# lvds_drv_e.net
KiCad netlist of a schematic drawn in Altium Designer
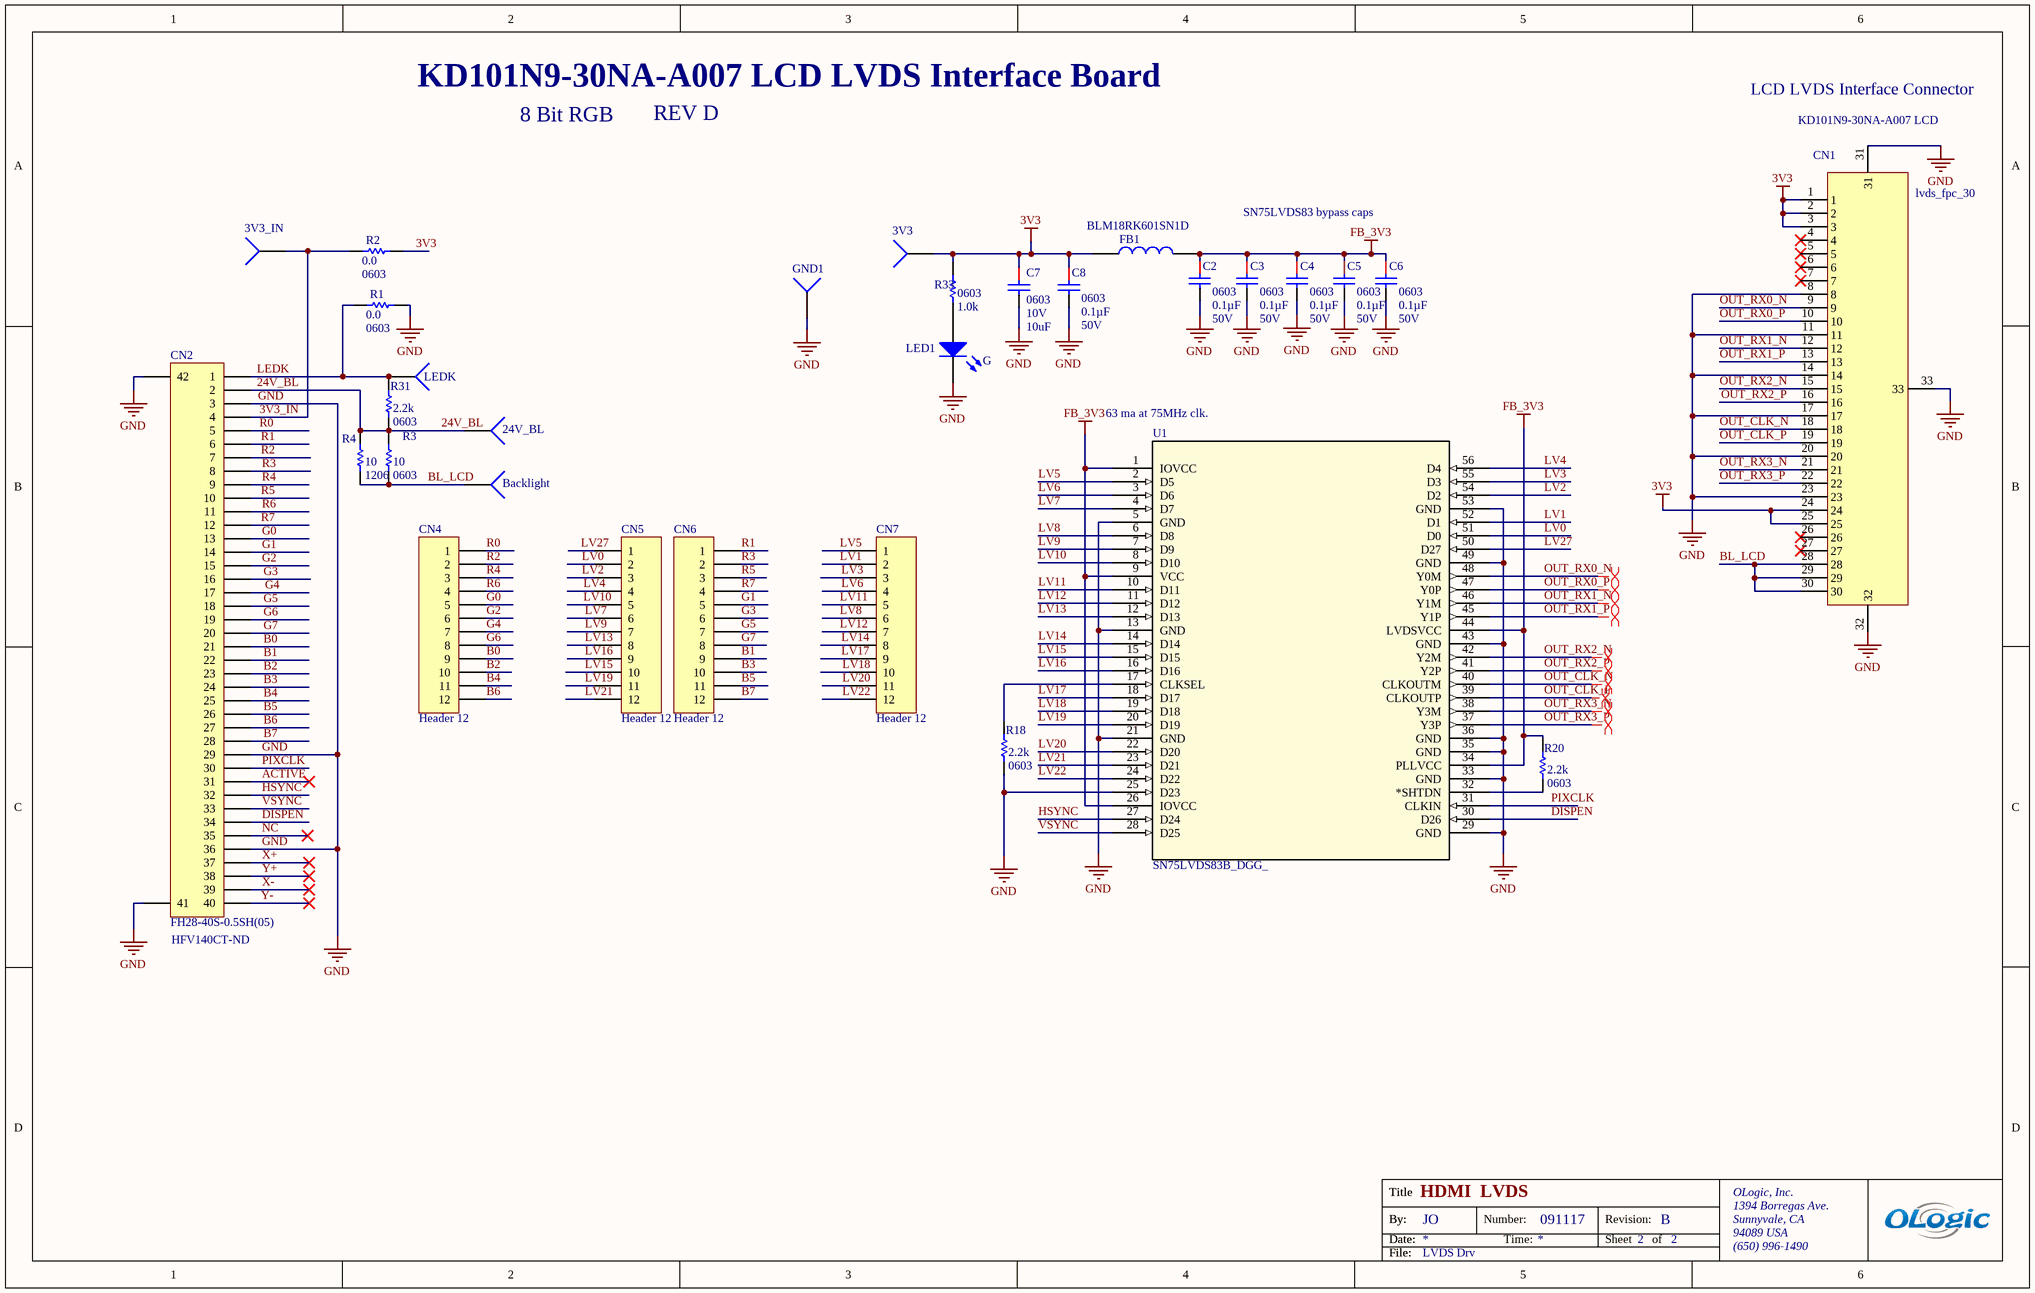
[diagram p0: lvds_drv_e.SchDoc]

(export (version "E")
  (design (tool "Eeschema 10.0.6"))
  (components
    (comp (ref "3V3")
      (value "~")
      (footprint "TestPoint-TH 35 mil")
      (description "Test Point")
      (libsource (lib "OLogic-Misc") (part "TestPoint"))
    )
    (comp (ref "3V3_IN")
      (value "~")
      (footprint "TestPoint-TH 35 mil")
      (description "Test Point")
      (libsource (lib "OLogic-Misc") (part "TestPoint"))
    )
    (comp (ref "24V_BL")
      (value "~")
      (footprint "TestPoint-TH 35 mil")
      (description "Test Point")
      (libsource (lib "OLogic-Misc") (part "TestPoint"))
    )
    (comp (ref "Backlight")
      (value "~")
      (footprint "TestPoint-TH 35 mil")
      (description "Test Point")
      (libsource (lib "OLogic-Misc") (part "TestPoint"))
    )
    (comp (ref "C2")
      (value "0.1uF 0603 50V")
      (footprint "CAPC0603(1608)_N")
      (fields
        (field (name "MANUFACTURER") "Yageo")
        (field (name "MANUFACTURER PART NUMBER") "CC0603ZRY5V9BB104")
        (field (name "TOLERANCE") "-20%, +80%")
        (field (name "PACKAGE / CASE") "0603")
        (field (name "CAPACITANCE") "0.1µF")
        (field (name "VOLTAGE - RATED") "50V")
      )
      (libsource (lib "OLogic-Passive") (part "CAP CER 0.1UF 50V 10% X7R 0603"))
    )
    (comp (ref "C3")
      (value "0.1uF 0603 50V")
      (footprint "CAPC0603(1608)_N")
      (fields
        (field (name "MANUFACTURER") "Yageo")
        (field (name "MANUFACTURER PART NUMBER") "CC0603ZRY5V9BB104")
        (field (name "TOLERANCE") "-20%, +80%")
        (field (name "PACKAGE / CASE") "0603")
        (field (name "CAPACITANCE") "0.1µF")
        (field (name "VOLTAGE - RATED") "50V")
      )
      (libsource (lib "OLogic-Passive") (part "CAP CER 0.1UF 50V 10% X7R 0603"))
    )
    (comp (ref "C4")
      (value "0.1uF 0603 50V")
      (footprint "CAPC0603(1608)_N")
      (fields
        (field (name "MANUFACTURER") "Yageo")
        (field (name "MANUFACTURER PART NUMBER") "CC0603ZRY5V9BB104")
        (field (name "TOLERANCE") "-20%, +80%")
        (field (name "PACKAGE / CASE") "0603")
        (field (name "CAPACITANCE") "0.1µF")
        (field (name "VOLTAGE - RATED") "50V")
      )
      (libsource (lib "OLogic-Passive") (part "CAP CER 0.1UF 50V 10% X7R 0603"))
    )
    (comp (ref "C5")
      (value "0.1uF 0603 50V")
      (footprint "CAPC0603(1608)_N")
      (fields
        (field (name "MANUFACTURER") "Yageo")
        (field (name "MANUFACTURER PART NUMBER") "CC0603ZRY5V9BB104")
        (field (name "TOLERANCE") "-20%, +80%")
        (field (name "PACKAGE / CASE") "0603")
        (field (name "CAPACITANCE") "0.1µF")
        (field (name "VOLTAGE - RATED") "50V")
      )
      (libsource (lib "OLogic-Passive") (part "CAP CER 0.1UF 50V 10% X7R 0603"))
    )
    (comp (ref "C6")
      (value "0.1uF 0603 50V")
      (footprint "CAPC0603(1608)_N")
      (fields
        (field (name "MANUFACTURER") "Yageo")
        (field (name "MANUFACTURER PART NUMBER") "CC0603ZRY5V9BB104")
        (field (name "TOLERANCE") "-20%, +80%")
        (field (name "PACKAGE / CASE") "0603")
        (field (name "CAPACITANCE") "0.1µF")
        (field (name "VOLTAGE - RATED") "50V")
      )
      (libsource (lib "OLogic-Passive") (part "CAP CER 0.1UF 50V 10% X7R 0603"))
    )
    (comp (ref "C7")
      (value "CAP 10UF 10V 10% X5R 0603")
      (footprint "CAPC0603(1608)_N")
      (description "10uF 0603")
      (fields
        (field (name "MANUFACTURER") "Samsung Electro-Mechanics America, Inc")
        (field (name "MANUFACTURER PART NUMBER") "CL10A106KP8NNNC")
        (field (name "PACKAGE / CASE") "0603")
        (field (name "VOLTAGE - RATED") "10V")
        (field (name "CAPACITANCE") "10uF")
      )
      (libsource (lib "OLogic-Passive") (part "CAP CER 10UF 10V 10% X5R 0603"))
    )
    (comp (ref "C8")
      (value "0.1uF 0603 50V")
      (footprint "CAPC0603(1608)_N")
      (fields
        (field (name "MANUFACTURER") "Yageo")
        (field (name "MANUFACTURER PART NUMBER") "CC0603ZRY5V9BB104")
        (field (name "TOLERANCE") "-20%, +80%")
        (field (name "PACKAGE / CASE") "0603")
        (field (name "CAPACITANCE") "0.1µF")
        (field (name "VOLTAGE - RATED") "50V")
      )
      (libsource (lib "OLogic-Passive") (part "CAP CER 0.1UF 50V 10% X7R 0603"))
    )
    (comp (ref "CN1")
      (value "lvds_fpc_30")
      (footprint "LVDS_FPC_30")
      (libsource (lib "hdmi_lvds") (part "lvds_fpc_30"))
    )
    (comp (ref "CN2")
      (value "FH28-40S-0.5SH(05)")
      (footprint "FH28-40S-0.5SH(05)")
      (description "Flex Cable, 40P, 0.5mm Pitch")
      (fields (field (name "MANUFACTURER") "Hirose Electric Co Ltd"))
      (libsource (lib "OLogic-Connectors") (part "FH28-40S-0.5SH(05)"))
    )
    (comp (ref "CN4")
      (value "Header 12")
      (footprint "HDR1X12")
      (description "Header, 12-Pin")
      (fields (field (name "PUBLISHER") "Altium Limited"))
      (libsource (lib "OLogic-Connectors") (part "Header 12"))
    )
    (comp (ref "CN5")
      (value "Header 12")
      (footprint "HDR1X12")
      (description "Header, 12-Pin")
      (fields (field (name "PUBLISHER") "Altium Limited"))
      (libsource (lib "") (part "Header 12_1"))
    )
    (comp (ref "CN6")
      (value "Header 12")
      (footprint "HDR1X12")
      (description "Header, 12-Pin")
      (fields (field (name "PUBLISHER") "Altium Limited"))
      (libsource (lib "OLogic-Connectors") (part "Header 12"))
    )
    (comp (ref "CN7")
      (value "Header 12")
      (footprint "HDR1X12")
      (description "Header, 12-Pin")
      (fields (field (name "PUBLISHER") "Altium Limited"))
      (libsource (lib "") (part "Header 12_1"))
    )
    (comp (ref "FB1")
      (value "BLM18RK601SN1D")
      (footprint "RESC0603(1608)_N")
      (description "FERRITE 120 OHM 0603 500mA")
      (fields
        (field (name "MANUFACTURER") "TDK Corporation")
        (field (name "MANUFACTURER PART NUMBER") "MMZ1608R121ATA00")
        (field (name "CREATOR") "*")
      )
      (libsource (lib "OLogic-Passive") (part "FERRITE BEAD 120 OHM 0603 1LN"))
    )
    (comp (ref "GND1")
      (value "~")
      (footprint "TestPoint-TH 35 mil")
      (description "Test Point")
      (libsource (lib "OLogic-Misc") (part "TestPoint"))
    )
    (comp (ref "LED1")
      (value "G")
      (footprint "SM-LED-0603")
      (description "0603 SMD LED")
      (libsource (lib "OLogic-Diode-Opto-LED") (part "0603 LED"))
    )
    (comp (ref "LEDK")
      (value "~")
      (footprint "TestPoint-TH 35 mil")
      (description "Test Point")
      (libsource (lib "OLogic-Misc") (part "TestPoint"))
    )
    (comp (ref "R1")
      (value "0")
      (footprint "RESC0603(1608)_N")
      (description "0 0603")
      (fields
        (field (name "MANUFACTURER") "Panasonic Electronic Components")
        (field (name "MANUFACTURER PART NUMBER") "ERJ-3GEY0R00V")
        (field (name "RESISTANCE (OHMS)") "0.0")
        (field (name "PACKAGE / CASE") "0603")
      )
      (libsource (lib "OLogic-Passive") (part "RES 0.0 OHM 1/10W JUMP 0603 SMD"))
    )
    (comp (ref "R2")
      (value "0")
      (footprint "RESC0603(1608)_N")
      (description "0 0603")
      (fields
        (field (name "MANUFACTURER") "Panasonic Electronic Components")
        (field (name "MANUFACTURER PART NUMBER") "ERJ-3GEY0R00V")
        (field (name "RESISTANCE (OHMS)") "0.0")
        (field (name "PACKAGE / CASE") "0603")
      )
      (libsource (lib "OLogic-Passive") (part "RES 0.0 OHM 1/10W JUMP 0603 SMD"))
    )
    (comp (ref "R3")
      (value "10")
      (footprint "RESC0805(2012)_N")
      (description "10 0603")
      (fields
        (field (name "MANUFACTURER") "Panasonic Electronic Components")
        (field (name "MANUFACTURER PART NUMBER") "ERJ-3EKF10R0V")
        (field (name "RESISTANCE (OHMS)") "10")
        (field (name "PACKAGE / CASE") "0603")
      )
      (libsource (lib "OLogic-Passive") (part "RES 10 OHM 1/10W 1% 0603 SMD"))
    )
    (comp (ref "R4")
      (value "10")
      (footprint "RESC1206(3216)_N")
      (description "10 1206")
      (fields
        (field (name "MANUFACTURER") "Panasonic Electronic Components")
        (field (name "MANUFACTURER PART NUMBER") "ERJ-8ENF10R0V")
        (field (name "RESISTANCE (OHMS)") "10")
        (field (name "PACKAGE / CASE") "1206")
      )
      (libsource (lib "OLogic-Passive") (part "RES 10 OHM 1/4W 1% 1206 SMD"))
    )
    (comp (ref "R18")
      (value "2.2K")
      (footprint "RESC0603(1608)_N")
      (description "2.2K 0603")
      (fields
        (field (name "MANUFACTURER") "Panasonic Electronic Components")
        (field (name "MANUFACTURER PART NUMBER") "ERJ-3GEYJ222V")
        (field (name "RESISTANCE (OHMS)") "2.2k")
        (field (name "PACKAGE / CASE") "0603")
      )
      (libsource (lib "OLogic-Passive") (part "RES 2.2K OHM 1/10W 5% 0603 SMD"))
    )
    (comp (ref "R20")
      (value "2.2K")
      (footprint "RESC0603(1608)_N")
      (description "2.2K 0603")
      (fields
        (field (name "MANUFACTURER") "Panasonic Electronic Components")
        (field (name "MANUFACTURER PART NUMBER") "ERJ-3GEYJ222V")
        (field (name "RESISTANCE (OHMS)") "2.2k")
        (field (name "PACKAGE / CASE") "0603")
      )
      (libsource (lib "OLogic-Passive") (part "RES 2.2K OHM 1/10W 5% 0603 SMD"))
    )
    (comp (ref "R31")
      (value "2.2K")
      (footprint "RESC0603(1608)_N")
      (description "2.2K 0603")
      (fields
        (field (name "MANUFACTURER") "Panasonic Electronic Components")
        (field (name "MANUFACTURER PART NUMBER") "ERJ-3GEYJ222V")
        (field (name "RESISTANCE (OHMS)") "2.2k")
        (field (name "PACKAGE / CASE") "0603")
      )
      (libsource (lib "OLogic-Passive") (part "RES 2.2K OHM 1/10W 5% 0603 SMD"))
    )
    (comp (ref "R33")
      (value "1.0K")
      (footprint "RESC0603(1608)_N")
      (description "1.0K 0603")
      (fields
        (field (name "MANUFACTURER") "Stackpole Electronics Inc.")
        (field (name "MANUFACTURER PART NUMBER") "RMCF0603FT1K00")
        (field (name "PACKAGE / CASE") "0603")
        (field (name "RESISTANCE (OHMS)") "1.0k")
      )
      (libsource (lib "OLogic-Passive") (part "RES 1K OHM 1% 1/10W 0603"))
    )
    (comp (ref "U1")
      (value "SN75LVDS83B_DGG_")
      (footprint "DGG56")
      (description "Imported")
      (fields
        (field (name "MANUFACTURER") "Texas Instruments")
        (field (name "GENERIC_PART_NUMBER") "SN75LVDS83B")
      )
      (libsource (lib "lab power supply") (part "SN75LVDS83B_DGG_"))
    )
  )
  (nets
    (net (code "1") (name "/3V3_IN") (class "Default")
      (node (ref "3V3_IN") (pin "1") (pinfunction "1_1") (pintype "passive"))
      (node (ref "CN2") (pin "4") (pinfunction "4_4") (pintype "passive"))
      (node (ref "R2") (pin "2") (pinfunction "2_2") (pintype "passive"))
    )
    (net (code "2") (name "/24V_BL") (class "Default")
      (node (ref "24V_BL") (pin "1") (pinfunction "1_1") (pintype "passive"))
      (node (ref "CN2") (pin "2") (pinfunction "2_2") (pintype "passive"))
      (node (ref "R3") (pin "2") (pinfunction "2_2") (pintype "passive"))
      (node (ref "R31") (pin "2") (pinfunction "2_2") (pintype "passive"))
      (node (ref "R4") (pin "2") (pinfunction "2_2") (pintype "passive"))
    )
    (net (code "3") (name "/ACTIVE") (class "Default")
      (node (ref "CN2") (pin "31") (pinfunction "31_31") (pintype "passive+no_connect"))
    )
    (net (code "4") (name "/B0") (class "Default")
      (node (ref "CN2") (pin "21") (pinfunction "21_21") (pintype "passive"))
      (node (ref "CN4") (pin "9") (pinfunction "9_9") (pintype "passive"))
    )
    (net (code "5") (name "/B1") (class "Default")
      (node (ref "CN2") (pin "22") (pinfunction "22_22") (pintype "passive"))
      (node (ref "CN6") (pin "9") (pinfunction "9_9") (pintype "passive"))
    )
    (net (code "6") (name "/B2") (class "Default")
      (node (ref "CN2") (pin "23") (pinfunction "23_23") (pintype "passive"))
      (node (ref "CN4") (pin "10") (pinfunction "10_10") (pintype "passive"))
    )
    (net (code "7") (name "/B3") (class "Default")
      (node (ref "CN2") (pin "24") (pinfunction "24_24") (pintype "passive"))
      (node (ref "CN6") (pin "10") (pinfunction "10_10") (pintype "passive"))
    )
    (net (code "8") (name "/B4") (class "Default")
      (node (ref "CN2") (pin "25") (pinfunction "25_25") (pintype "passive"))
      (node (ref "CN4") (pin "11") (pinfunction "11_11") (pintype "passive"))
    )
    (net (code "9") (name "/B5") (class "Default")
      (node (ref "CN2") (pin "26") (pinfunction "26_26") (pintype "passive"))
      (node (ref "CN6") (pin "11") (pinfunction "11_11") (pintype "passive"))
    )
    (net (code "10") (name "/B6") (class "Default")
      (node (ref "CN2") (pin "27") (pinfunction "27_27") (pintype "passive"))
      (node (ref "CN4") (pin "12") (pinfunction "12_12") (pintype "passive"))
    )
    (net (code "11") (name "/B7") (class "Default")
      (node (ref "CN2") (pin "28") (pinfunction "28_28") (pintype "passive"))
      (node (ref "CN6") (pin "12") (pinfunction "12_12") (pintype "passive"))
    )
    (net (code "12") (name "/BL_LCD") (class "Default")
      (node (ref "Backlight") (pin "1") (pinfunction "1_1") (pintype "passive"))
      (node (ref "CN1") (pin "28") (pinfunction "28_28") (pintype "passive"))
      (node (ref "CN1") (pin "29") (pinfunction "29_29") (pintype "passive"))
      (node (ref "CN1") (pin "30") (pinfunction "30_30") (pintype "passive"))
      (node (ref "R3") (pin "1") (pinfunction "1_1") (pintype "passive"))
      (node (ref "R4") (pin "1") (pinfunction "1_1") (pintype "passive"))
    )
    (net (code "13") (name "/DISPEN") (class "Default")
      (node (ref "CN2") (pin "34") (pinfunction "34_34") (pintype "passive"))
      (node (ref "U1") (pin "30") (pinfunction "D26_30") (pintype "input"))
    )
    (net (code "14") (name "/G0") (class "Default")
      (node (ref "CN2") (pin "13") (pinfunction "13_13") (pintype "passive"))
      (node (ref "CN4") (pin "5") (pinfunction "5_5") (pintype "passive"))
    )
    (net (code "15") (name "/G1") (class "Default")
      (node (ref "CN2") (pin "14") (pinfunction "14_14") (pintype "passive"))
      (node (ref "CN6") (pin "5") (pinfunction "5_5") (pintype "passive"))
    )
    (net (code "16") (name "/G2") (class "Default")
      (node (ref "CN2") (pin "15") (pinfunction "15_15") (pintype "passive"))
      (node (ref "CN4") (pin "6") (pinfunction "6_6") (pintype "passive"))
    )
    (net (code "17") (name "/G3") (class "Default")
      (node (ref "CN2") (pin "16") (pinfunction "16_16") (pintype "passive"))
      (node (ref "CN6") (pin "6") (pinfunction "6_6") (pintype "passive"))
    )
    (net (code "18") (name "/G4") (class "Default")
      (node (ref "CN2") (pin "17") (pinfunction "17_17") (pintype "passive"))
      (node (ref "CN4") (pin "7") (pinfunction "7_7") (pintype "passive"))
    )
    (net (code "19") (name "/G5") (class "Default")
      (node (ref "CN2") (pin "18") (pinfunction "18_18") (pintype "passive"))
      (node (ref "CN6") (pin "7") (pinfunction "7_7") (pintype "passive"))
    )
    (net (code "20") (name "/G6") (class "Default")
      (node (ref "CN2") (pin "19") (pinfunction "19_19") (pintype "passive"))
      (node (ref "CN4") (pin "8") (pinfunction "8_8") (pintype "passive"))
    )
    (net (code "21") (name "/G7") (class "Default")
      (node (ref "CN2") (pin "20") (pinfunction "20_20") (pintype "passive"))
      (node (ref "CN6") (pin "8") (pinfunction "8_8") (pintype "passive"))
    )
    (net (code "22") (name "/HSYNC") (class "Default")
      (node (ref "CN2") (pin "32") (pinfunction "32_32") (pintype "passive"))
      (node (ref "U1") (pin "27") (pinfunction "D24_27") (pintype "input"))
    )
    (net (code "23") (name "/LEDK") (class "Default")
      (node (ref "CN2") (pin "1") (pinfunction "1_1") (pintype "passive"))
      (node (ref "LEDK") (pin "1") (pinfunction "1_1") (pintype "passive"))
      (node (ref "R1") (pin "2") (pinfunction "2_2") (pintype "passive"))
      (node (ref "R31") (pin "1") (pinfunction "1_1") (pintype "passive"))
    )
    (net (code "24") (name "/LV0") (class "Default")
      (node (ref "CN5") (pin "2") (pinfunction "2_2") (pintype "passive"))
      (node (ref "U1") (pin "51") (pinfunction "D0_51") (pintype "input"))
    )
    (net (code "25") (name "/LV1") (class "Default")
      (node (ref "CN7") (pin "2") (pinfunction "2_2") (pintype "passive"))
      (node (ref "U1") (pin "52") (pinfunction "D1_52") (pintype "input"))
    )
    (net (code "26") (name "/LV2") (class "Default")
      (node (ref "CN5") (pin "3") (pinfunction "3_3") (pintype "passive"))
      (node (ref "U1") (pin "54") (pinfunction "D2_54") (pintype "input"))
    )
    (net (code "27") (name "/LV3") (class "Default")
      (node (ref "CN7") (pin "3") (pinfunction "3_3") (pintype "passive"))
      (node (ref "U1") (pin "55") (pinfunction "D3_55") (pintype "input"))
    )
    (net (code "28") (name "/LV4") (class "Default")
      (node (ref "CN5") (pin "4") (pinfunction "4_4") (pintype "passive"))
      (node (ref "U1") (pin "56") (pinfunction "D4_56") (pintype "input"))
    )
    (net (code "29") (name "/LV5") (class "Default")
      (node (ref "CN7") (pin "1") (pinfunction "1_1") (pintype "passive"))
      (node (ref "U1") (pin "2") (pinfunction "D5_2") (pintype "input"))
    )
    (net (code "30") (name "/LV6") (class "Default")
      (node (ref "CN7") (pin "4") (pinfunction "4_4") (pintype "passive"))
      (node (ref "U1") (pin "3") (pinfunction "D6_3") (pintype "input"))
    )
    (net (code "31") (name "/LV7") (class "Default")
      (node (ref "CN5") (pin "6") (pinfunction "6_6") (pintype "passive"))
      (node (ref "U1") (pin "4") (pinfunction "D7_4") (pintype "input"))
    )
    (net (code "32") (name "/LV8") (class "Default")
      (node (ref "CN7") (pin "6") (pinfunction "6_6") (pintype "passive"))
      (node (ref "U1") (pin "6") (pinfunction "D8_6") (pintype "input"))
    )
    (net (code "33") (name "/LV9") (class "Default")
      (node (ref "CN5") (pin "7") (pinfunction "7_7") (pintype "passive"))
      (node (ref "U1") (pin "7") (pinfunction "D9_7") (pintype "input"))
    )
    (net (code "34") (name "/LV10") (class "Default")
      (node (ref "CN5") (pin "5") (pinfunction "5_5") (pintype "passive"))
      (node (ref "U1") (pin "8") (pinfunction "D10_8") (pintype "input"))
    )
    (net (code "35") (name "/LV11") (class "Default")
      (node (ref "CN7") (pin "5") (pinfunction "5_5") (pintype "passive"))
      (node (ref "U1") (pin "10") (pinfunction "D11_10") (pintype "input"))
    )
    (net (code "36") (name "/LV12") (class "Default")
      (node (ref "CN7") (pin "7") (pinfunction "7_7") (pintype "passive"))
      (node (ref "U1") (pin "11") (pinfunction "D12_11") (pintype "input"))
    )
    (net (code "37") (name "/LV13") (class "Default")
      (node (ref "CN5") (pin "8") (pinfunction "8_8") (pintype "passive"))
      (node (ref "U1") (pin "12") (pinfunction "D13_12") (pintype "input"))
    )
    (net (code "38") (name "/LV14") (class "Default")
      (node (ref "CN7") (pin "8") (pinfunction "8_8") (pintype "passive"))
      (node (ref "U1") (pin "14") (pinfunction "D14_14") (pintype "input"))
    )
    (net (code "39") (name "/LV15") (class "Default")
      (node (ref "CN5") (pin "10") (pinfunction "10_10") (pintype "passive"))
      (node (ref "U1") (pin "15") (pinfunction "D15_15") (pintype "input"))
    )
    (net (code "40") (name "/LV16") (class "Default")
      (node (ref "CN5") (pin "9") (pinfunction "9_9") (pintype "passive"))
      (node (ref "U1") (pin "16") (pinfunction "D16_16") (pintype "input"))
    )
    (net (code "41") (name "/LV17") (class "Default")
      (node (ref "CN7") (pin "9") (pinfunction "9_9") (pintype "passive"))
      (node (ref "U1") (pin "18") (pinfunction "D17_18") (pintype "input"))
    )
    (net (code "42") (name "/LV18") (class "Default")
      (node (ref "CN7") (pin "10") (pinfunction "10_10") (pintype "passive"))
      (node (ref "U1") (pin "19") (pinfunction "D18_19") (pintype "input"))
    )
    (net (code "43") (name "/LV19") (class "Default")
      (node (ref "CN5") (pin "11") (pinfunction "11_11") (pintype "passive"))
      (node (ref "U1") (pin "20") (pinfunction "D19_20") (pintype "input"))
    )
    (net (code "44") (name "/LV20") (class "Default")
      (node (ref "CN7") (pin "11") (pinfunction "11_11") (pintype "passive"))
      (node (ref "U1") (pin "22") (pinfunction "D20_22") (pintype "input"))
    )
    (net (code "45") (name "/LV21") (class "Default")
      (node (ref "CN5") (pin "12") (pinfunction "12_12") (pintype "passive"))
      (node (ref "U1") (pin "23") (pinfunction "D21_23") (pintype "input"))
    )
    (net (code "46") (name "/LV22") (class "Default")
      (node (ref "CN7") (pin "12") (pinfunction "12_12") (pintype "passive"))
      (node (ref "U1") (pin "24") (pinfunction "D22_24") (pintype "input"))
    )
    (net (code "47") (name "/LV27") (class "Default")
      (node (ref "CN5") (pin "1") (pinfunction "1_1") (pintype "passive"))
      (node (ref "U1") (pin "50") (pinfunction "D27_50") (pintype "input"))
    )
    (net (code "48") (name "/NC") (class "Default")
      (node (ref "CN2") (pin "35") (pinfunction "35_35") (pintype "passive+no_connect"))
    )
    (net (code "49") (name "/OUT_CLK_N") (class "Default")
      (node (ref "CN1") (pin "18") (pinfunction "18_18") (pintype "passive"))
      (node (ref "U1") (pin "40") (pinfunction "CLKOUTM_40") (pintype "output"))
    )
    (net (code "50") (name "/OUT_CLK_P") (class "Default")
      (node (ref "CN1") (pin "19") (pinfunction "19_19") (pintype "passive"))
      (node (ref "U1") (pin "39") (pinfunction "CLKOUTP_39") (pintype "output"))
    )
    (net (code "51") (name "/OUT_RX0_N") (class "Default")
      (node (ref "CN1") (pin "9") (pinfunction "9_9") (pintype "passive"))
      (node (ref "U1") (pin "48") (pinfunction "Y0M_48") (pintype "output"))
    )
    (net (code "52") (name "/OUT_RX0_P") (class "Default")
      (node (ref "CN1") (pin "10") (pinfunction "10_10") (pintype "passive"))
      (node (ref "U1") (pin "47") (pinfunction "Y0P_47") (pintype "output"))
    )
    (net (code "53") (name "/OUT_RX1_N") (class "Default")
      (node (ref "CN1") (pin "12") (pinfunction "12_12") (pintype "passive"))
      (node (ref "U1") (pin "46") (pinfunction "Y1M_46") (pintype "output"))
    )
    (net (code "54") (name "/OUT_RX1_P") (class "Default")
      (node (ref "CN1") (pin "13") (pinfunction "13_13") (pintype "passive"))
      (node (ref "U1") (pin "45") (pinfunction "Y1P_45") (pintype "output"))
    )
    (net (code "55") (name "/OUT_RX2_N") (class "Default")
      (node (ref "CN1") (pin "15") (pinfunction "15_15") (pintype "passive"))
      (node (ref "U1") (pin "42") (pinfunction "Y2M_42") (pintype "output"))
    )
    (net (code "56") (name "/OUT_RX2_P") (class "Default")
      (node (ref "CN1") (pin "16") (pinfunction "16_16") (pintype "passive"))
      (node (ref "U1") (pin "41") (pinfunction "Y2P_41") (pintype "output"))
    )
    (net (code "57") (name "/OUT_RX3_N") (class "Default")
      (node (ref "CN1") (pin "21") (pinfunction "21_21") (pintype "passive"))
      (node (ref "U1") (pin "38") (pinfunction "Y3M_38") (pintype "output"))
    )
    (net (code "58") (name "/OUT_RX3_P") (class "Default")
      (node (ref "CN1") (pin "22") (pinfunction "22_22") (pintype "passive"))
      (node (ref "U1") (pin "37") (pinfunction "Y3P_37") (pintype "output"))
    )
    (net (code "59") (name "/PIXCLK") (class "Default")
      (node (ref "CN2") (pin "30") (pinfunction "30_30") (pintype "passive"))
      (node (ref "U1") (pin "31") (pinfunction "CLKIN_31") (pintype "input"))
    )
    (net (code "60") (name "/R0") (class "Default")
      (node (ref "CN2") (pin "5") (pinfunction "5_5") (pintype "passive"))
      (node (ref "CN4") (pin "1") (pinfunction "1_1") (pintype "passive"))
    )
    (net (code "61") (name "/R1") (class "Default")
      (node (ref "CN2") (pin "6") (pinfunction "6_6") (pintype "passive"))
      (node (ref "CN6") (pin "1") (pinfunction "1_1") (pintype "passive"))
    )
    (net (code "62") (name "/R2") (class "Default")
      (node (ref "CN2") (pin "7") (pinfunction "7_7") (pintype "passive"))
      (node (ref "CN4") (pin "2") (pinfunction "2_2") (pintype "passive"))
    )
    (net (code "63") (name "/R3") (class "Default")
      (node (ref "CN2") (pin "8") (pinfunction "8_8") (pintype "passive"))
      (node (ref "CN6") (pin "2") (pinfunction "2_2") (pintype "passive"))
    )
    (net (code "64") (name "/R4") (class "Default")
      (node (ref "CN2") (pin "9") (pinfunction "9_9") (pintype "passive"))
      (node (ref "CN4") (pin "3") (pinfunction "3_3") (pintype "passive"))
    )
    (net (code "65") (name "/R5") (class "Default")
      (node (ref "CN2") (pin "10") (pinfunction "10_10") (pintype "passive"))
      (node (ref "CN6") (pin "3") (pinfunction "3_3") (pintype "passive"))
    )
    (net (code "66") (name "/R6") (class "Default")
      (node (ref "CN2") (pin "11") (pinfunction "11_11") (pintype "passive"))
      (node (ref "CN4") (pin "4") (pinfunction "4_4") (pintype "passive"))
    )
    (net (code "67") (name "/R7") (class "Default")
      (node (ref "CN2") (pin "12") (pinfunction "12_12") (pintype "passive"))
      (node (ref "CN6") (pin "4") (pinfunction "4_4") (pintype "passive"))
    )
    (net (code "68") (name "/VSYNC") (class "Default")
      (node (ref "CN2") (pin "33") (pinfunction "33_33") (pintype "passive"))
      (node (ref "U1") (pin "28") (pinfunction "D25_28") (pintype "input"))
    )
    (net (code "69") (name "/X+") (class "Default")
      (node (ref "CN2") (pin "37") (pinfunction "37_37") (pintype "passive+no_connect"))
    )
    (net (code "70") (name "/X-") (class "Default")
      (node (ref "CN2") (pin "39") (pinfunction "39_39") (pintype "passive+no_connect"))
    )
    (net (code "71") (name "/Y+") (class "Default")
      (node (ref "CN2") (pin "38") (pinfunction "38_38") (pintype "passive+no_connect"))
    )
    (net (code "72") (name "/Y-") (class "Default")
      (node (ref "CN2") (pin "40") (pinfunction "40_40") (pintype "passive+no_connect"))
    )
    (net (code "73") (name "3V3") (class "Default")
      (node (ref "3V3") (pin "1") (pinfunction "1_1") (pintype "passive"))
      (node (ref "C7") (pin "1") (pinfunction "1_1") (pintype "passive"))
      (node (ref "C8") (pin "1") (pinfunction "1_1") (pintype "passive"))
      (node (ref "CN1") (pin "1") (pinfunction "1_1") (pintype "passive"))
      (node (ref "CN1") (pin "2") (pinfunction "2_2") (pintype "passive"))
      (node (ref "CN1") (pin "24") (pinfunction "24_24") (pintype "passive"))
      (node (ref "CN1") (pin "25") (pinfunction "25_25") (pintype "passive"))
      (node (ref "CN1") (pin "3") (pinfunction "3_3") (pintype "passive"))
      (node (ref "FB1") (pin "1") (pinfunction "1_1") (pintype "passive"))
      (node (ref "R2") (pin "1") (pinfunction "1_1") (pintype "passive"))
      (node (ref "R33") (pin "1") (pinfunction "1_1") (pintype "passive"))
    )
    (net (code "74") (name "FB_3V3") (class "Default")
      (node (ref "C2") (pin "1") (pinfunction "1_1") (pintype "passive"))
      (node (ref "C3") (pin "1") (pinfunction "1_1") (pintype "passive"))
      (node (ref "C4") (pin "1") (pinfunction "1_1") (pintype "passive"))
      (node (ref "C5") (pin "1") (pinfunction "1_1") (pintype "passive"))
      (node (ref "C6") (pin "1") (pinfunction "1_1") (pintype "passive"))
      (node (ref "FB1") (pin "2") (pinfunction "2_2") (pintype "passive"))
      (node (ref "R20") (pin "1") (pinfunction "1_1") (pintype "passive"))
      (node (ref "U1") (pin "1") (pinfunction "IOVCC_1") (pintype "power_in"))
      (node (ref "U1") (pin "26") (pinfunction "IOVCC_26") (pintype "power_in"))
      (node (ref "U1") (pin "34") (pinfunction "PLLVCC_34") (pintype "power_in"))
      (node (ref "U1") (pin "44") (pinfunction "LVDSVCC_44") (pintype "power_in"))
      (node (ref "U1") (pin "9") (pinfunction "VCC_9") (pintype "power_in"))
    )
    (net (code "75") (name "GND") (class "Default")
      (node (ref "C2") (pin "2") (pinfunction "2_2") (pintype "passive"))
      (node (ref "C3") (pin "2") (pinfunction "2_2") (pintype "passive"))
      (node (ref "C4") (pin "2") (pinfunction "2_2") (pintype "passive"))
      (node (ref "C5") (pin "2") (pinfunction "2_2") (pintype "passive"))
      (node (ref "C6") (pin "2") (pinfunction "2_2") (pintype "passive"))
      (node (ref "C7") (pin "2") (pinfunction "2_2") (pintype "passive"))
      (node (ref "C8") (pin "2") (pinfunction "2_2") (pintype "passive"))
      (node (ref "CN1") (pin "11") (pinfunction "11_11") (pintype "passive"))
      (node (ref "CN1") (pin "14") (pinfunction "14_14") (pintype "passive"))
      (node (ref "CN1") (pin "17") (pinfunction "17_17") (pintype "passive"))
      (node (ref "CN1") (pin "20") (pinfunction "20_20") (pintype "passive"))
      (node (ref "CN1") (pin "23") (pinfunction "23_23") (pintype "passive"))
      (node (ref "CN1") (pin "31") (pinfunction "31_31") (pintype "passive"))
      (node (ref "CN1") (pin "32") (pinfunction "32_32") (pintype "passive"))
      (node (ref "CN1") (pin "33") (pinfunction "33_33") (pintype "passive"))
      (node (ref "CN1") (pin "8") (pinfunction "8_8") (pintype "passive"))
      (node (ref "CN2") (pin "29") (pinfunction "29_29") (pintype "passive"))
      (node (ref "CN2") (pin "3") (pinfunction "3_3") (pintype "passive"))
      (node (ref "CN2") (pin "36") (pinfunction "36_36") (pintype "passive"))
      (node (ref "CN2") (pin "41") (pinfunction "41_41") (pintype "passive"))
      (node (ref "CN2") (pin "42") (pinfunction "42_42") (pintype "passive"))
      (node (ref "GND1") (pin "1") (pinfunction "1_1") (pintype "passive"))
      (node (ref "LED1") (pin "2") (pinfunction "2_2") (pintype "passive"))
      (node (ref "R1") (pin "1") (pinfunction "1_1") (pintype "passive"))
      (node (ref "R18") (pin "2") (pinfunction "2_2") (pintype "passive"))
      (node (ref "U1") (pin "13") (pinfunction "GND_13") (pintype "power_in"))
      (node (ref "U1") (pin "21") (pinfunction "GND_21") (pintype "power_in"))
      (node (ref "U1") (pin "25") (pinfunction "D23_25") (pintype "input"))
      (node (ref "U1") (pin "29") (pinfunction "GND_29") (pintype "power_in"))
      (node (ref "U1") (pin "33") (pinfunction "GND_33") (pintype "power_in"))
      (node (ref "U1") (pin "35") (pinfunction "GND_35") (pintype "power_in"))
      (node (ref "U1") (pin "36") (pinfunction "GND_36") (pintype "power_in"))
      (node (ref "U1") (pin "43") (pinfunction "GND_43") (pintype "power_in"))
      (node (ref "U1") (pin "49") (pinfunction "GND_49") (pintype "power_in"))
      (node (ref "U1") (pin "5") (pinfunction "GND_5") (pintype "power_in"))
      (node (ref "U1") (pin "53") (pinfunction "GND_53") (pintype "power_in"))
    )
    (net (code "76") (name "Net-(LED1-Pad1)") (class "Default")
      (node (ref "LED1") (pin "1") (pinfunction "1_1") (pintype "passive"))
      (node (ref "R33") (pin "2") (pinfunction "2_2") (pintype "passive"))
    )
    (net (code "77") (name "Net-(U1-*SHTDN)") (class "Default")
      (node (ref "R20") (pin "2") (pinfunction "2_2") (pintype "passive"))
      (node (ref "U1") (pin "32") (pinfunction "*SHTDN_32") (pintype "power_in"))
    )
    (net (code "78") (name "Net-(U1-CLKSEL)") (class "Default")
      (node (ref "R18") (pin "1") (pinfunction "1_1") (pintype "passive"))
      (node (ref "U1") (pin "17") (pinfunction "CLKSEL_17") (pintype "input"))
    )
    (net (code "79") (name "unconnected-(CN1-Pad4)") (class "Default")
      (node (ref "CN1") (pin "4") (pinfunction "4_4") (pintype "passive+no_connect"))
    )
    (net (code "80") (name "unconnected-(CN1-Pad5)") (class "Default")
      (node (ref "CN1") (pin "5") (pinfunction "5_5") (pintype "passive+no_connect"))
    )
    (net (code "81") (name "unconnected-(CN1-Pad6)") (class "Default")
      (node (ref "CN1") (pin "6") (pinfunction "6_6") (pintype "passive+no_connect"))
    )
    (net (code "82") (name "unconnected-(CN1-Pad7)") (class "Default")
      (node (ref "CN1") (pin "7") (pinfunction "7_7") (pintype "passive+no_connect"))
    )
    (net (code "83") (name "unconnected-(CN1-Pad26)") (class "Default")
      (node (ref "CN1") (pin "26") (pinfunction "26_26") (pintype "passive+no_connect"))
    )
    (net (code "84") (name "unconnected-(CN1-Pad27)") (class "Default")
      (node (ref "CN1") (pin "27") (pinfunction "27_27") (pintype "passive+no_connect"))
    )
  )
)
